# UKU208_power_board.net
KiCad netlist of a schematic drawn in Altium Designer
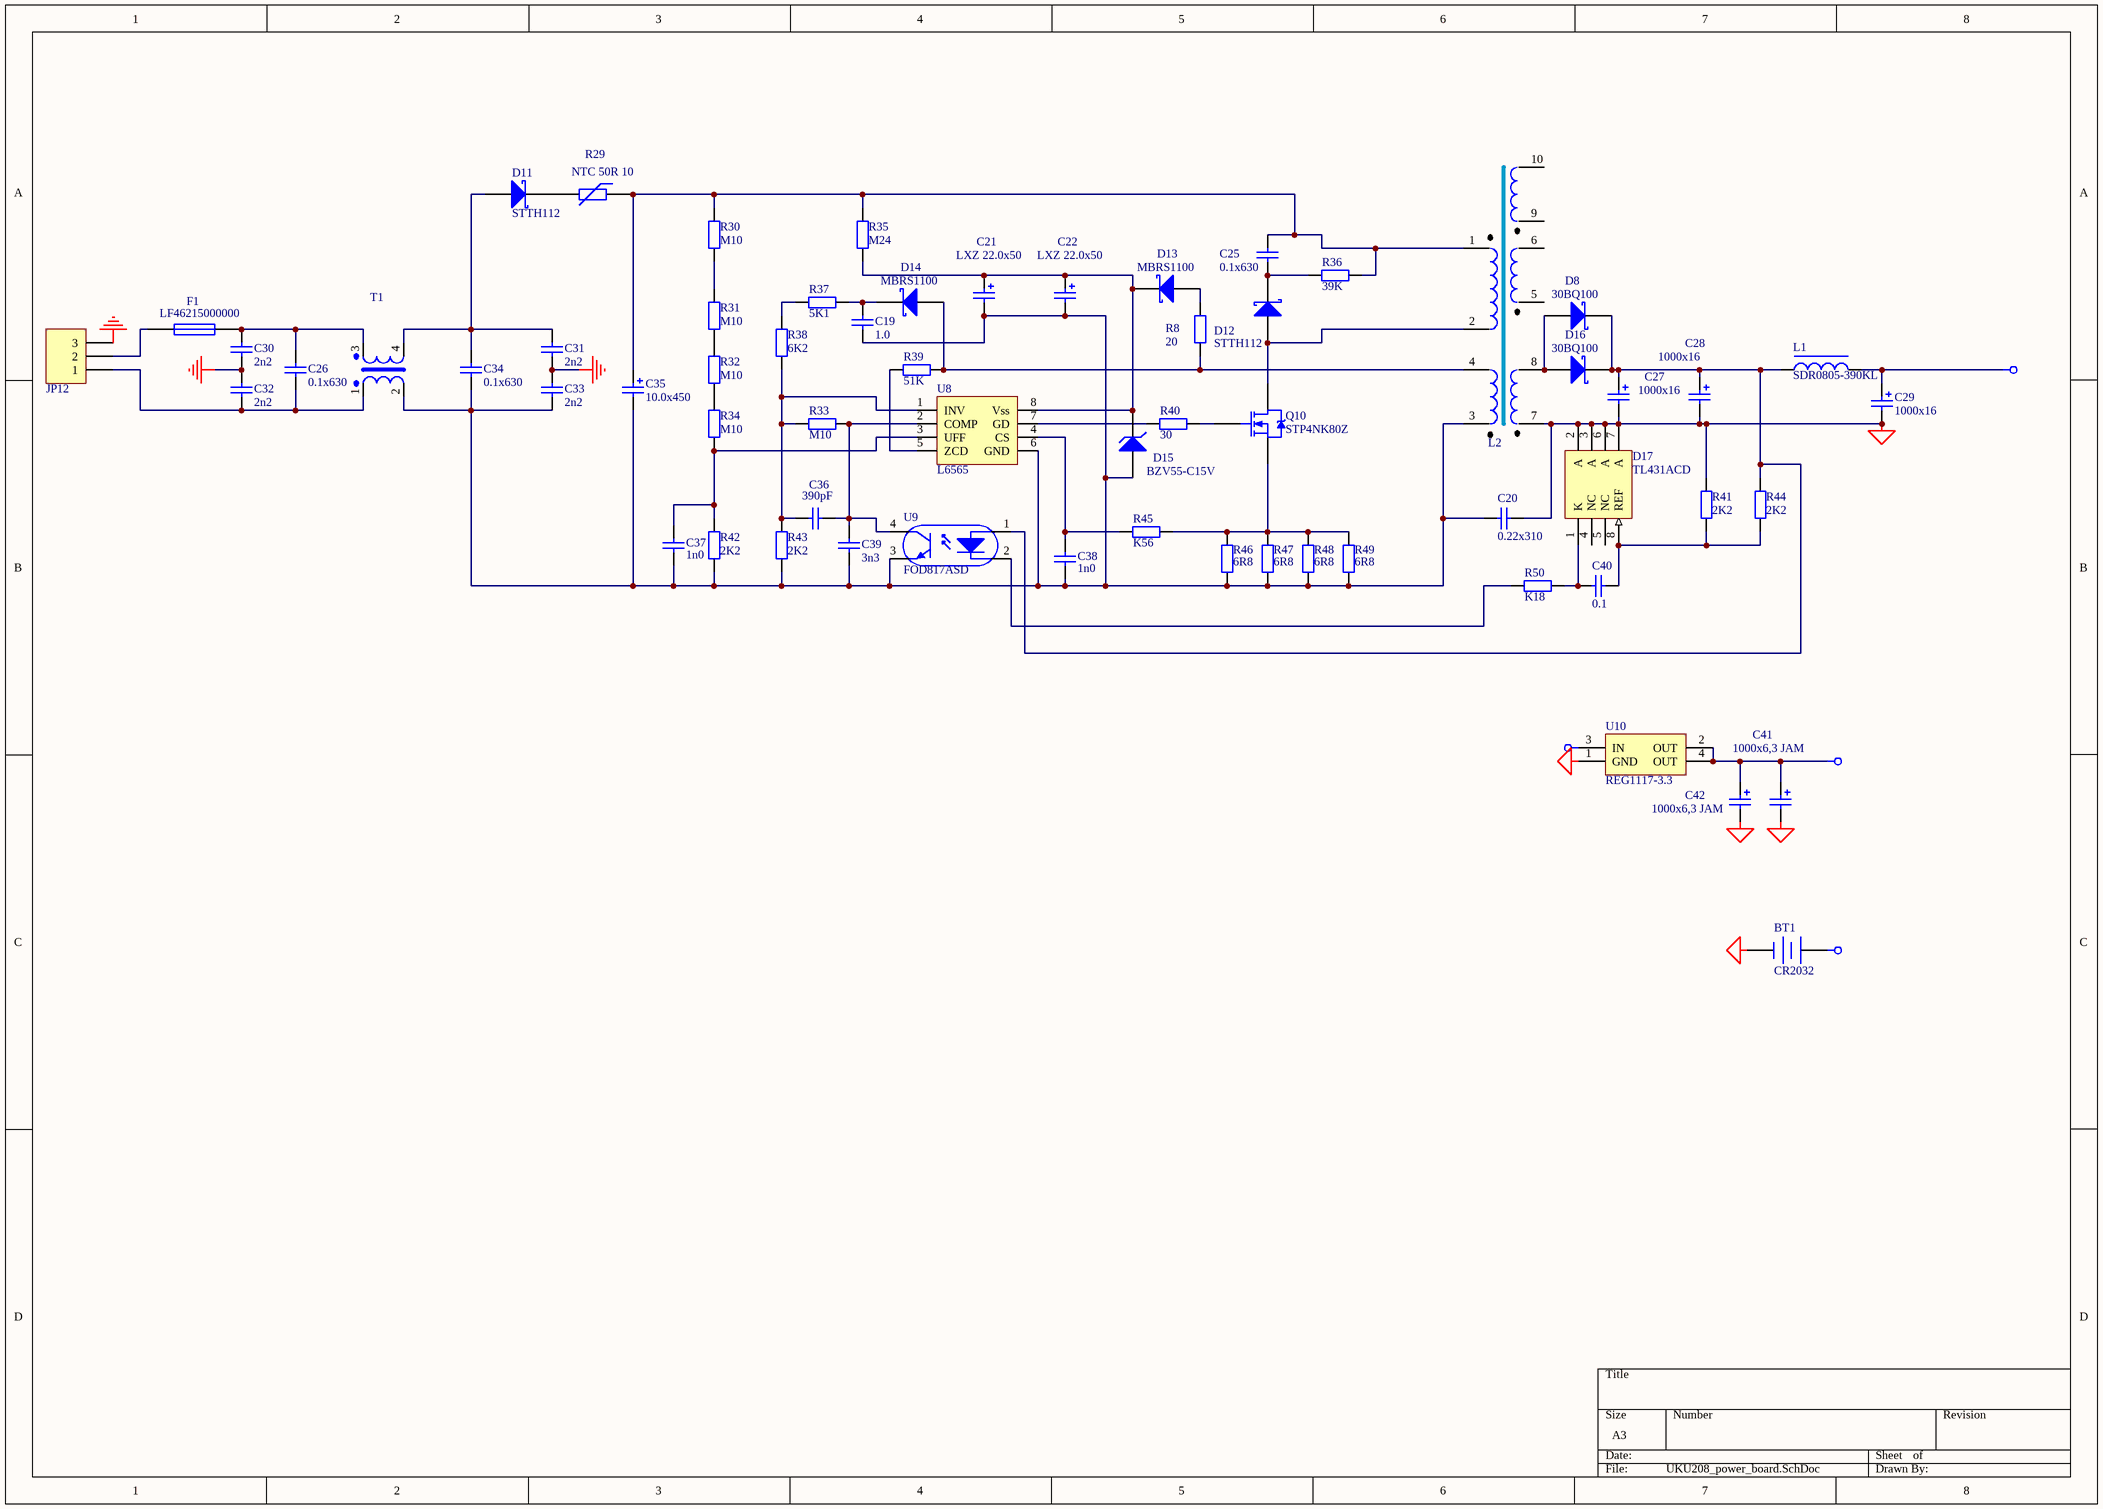
[diagram p0: UKU208_power_board.SchDoc]

(export (version "E")
  (design (tool "Eeschema 10.0.6"))
  (components
    (comp (ref "BT1")
      (value "CR2032")
      (footprint "BAT_SUPP")
      (description "Multicell Battery")
      (fields (field (name "MANUFACTURER") "Generic Components") (field (name "PUBLISHER") "Altium Limited"))
      (libsource (lib "Miscellaneous Devices") (part "Battery"))
    )
    (comp (ref "C19")
      (value "1.0")
      (footprint "_1206")
      (description "Capacitor (Semiconductor SIM Model)")
      (fields (field (name "MANUFACTURER") "Generic Components") (field (name "PUBLISHER") "Altium Limited"))
      (libsource (lib "Miscellaneous Devices") (part "Cap Semi"))
    )
    (comp (ref "C20")
      (value "0.22x310")
      (footprint "C8")
      (description "Capacitor (Semiconductor SIM Model)")
      (fields (field (name "MANUFACTURER") "Generic Components") (field (name "PUBLISHER") "Altium Limited"))
      (libsource (lib "Miscellaneous Devices") (part "Cap Semi"))
    )
    (comp (ref "C21")
      (value "LXZ 22.0x50")
      (footprint "el3")
      (description "Polarized Capacitor (Radial)")
      (fields (field (name "MANUFACTURER") "Generic Components") (field (name "PUBLISHER") "Altium Limited"))
      (libsource (lib "PAL") (part "Cap Pol1"))
    )
    (comp (ref "C22")
      (value "LXZ 22.0x50")
      (footprint "el3")
      (description "Polarized Capacitor (Radial)")
      (fields (field (name "MANUFACTURER") "Generic Components") (field (name "PUBLISHER") "Altium Limited"))
      (libsource (lib "PAL") (part "Cap Pol1"))
    )
    (comp (ref "C25")
      (value "0.1x630")
      (footprint "c15")
      (description "Capacitor (Semiconductor SIM Model)")
      (fields (field (name "MANUFACTURER") "Generic Components") (field (name "PUBLISHER") "Altium Limited"))
      (libsource (lib "Miscellaneous Devices") (part "Cap Semi"))
    )
    (comp (ref "C26")
      (value "0.1x630")
      (footprint "c15")
      (description "Capacitor (Semiconductor SIM Model)")
      (fields (field (name "MANUFACTURER") "Generic Components") (field (name "PUBLISHER") "Altium Limited"))
      (libsource (lib "Miscellaneous Devices") (part "Cap Semi"))
    )
    (comp (ref "C27")
      (value "1000x16")
      (footprint "el5")
      (description "Polarized Capacitor (Radial)")
      (fields (field (name "MANUFACTURER") "Generic Components") (field (name "PUBLISHER") "Altium Limited"))
      (libsource (lib "PAL") (part "Cap Pol1"))
    )
    (comp (ref "C28")
      (value "1000x16")
      (footprint "el5")
      (description "Polarized Capacitor (Radial)")
      (fields (field (name "MANUFACTURER") "Generic Components") (field (name "PUBLISHER") "Altium Limited"))
      (libsource (lib "PAL") (part "Cap Pol1"))
    )
    (comp (ref "C29")
      (value "1000x16")
      (footprint "el5")
      (description "Polarized Capacitor (Radial)")
      (fields (field (name "MANUFACTURER") "Generic Components") (field (name "PUBLISHER") "Altium Limited"))
      (libsource (lib "PAL") (part "Cap Pol1"))
    )
    (comp (ref "C30")
      (value "2n2")
      (footprint "C8")
      (description "Capacitor (Semiconductor SIM Model)")
      (fields (field (name "MANUFACTURER") "Generic Components") (field (name "PUBLISHER") "Altium Limited"))
      (libsource (lib "Miscellaneous Devices") (part "Cap Semi"))
    )
    (comp (ref "C31")
      (value "2n2")
      (footprint "c8")
      (description "Capacitor (Semiconductor SIM Model)")
      (fields (field (name "MANUFACTURER") "Generic Components") (field (name "PUBLISHER") "Altium Limited"))
      (libsource (lib "Miscellaneous Devices") (part "Cap Semi"))
    )
    (comp (ref "C32")
      (value "2n2")
      (footprint "c8")
      (description "Capacitor (Semiconductor SIM Model)")
      (fields (field (name "MANUFACTURER") "Generic Components") (field (name "PUBLISHER") "Altium Limited"))
      (libsource (lib "Miscellaneous Devices") (part "Cap Semi"))
    )
    (comp (ref "C33")
      (value "2n2")
      (footprint "c8")
      (description "Capacitor (Semiconductor SIM Model)")
      (fields (field (name "MANUFACTURER") "Generic Components") (field (name "PUBLISHER") "Altium Limited"))
      (libsource (lib "Miscellaneous Devices") (part "Cap Semi"))
    )
    (comp (ref "C34")
      (value "0.1x630")
      (footprint "c15")
      (description "Capacitor (Semiconductor SIM Model)")
      (fields (field (name "MANUFACTURER") "Generic Components") (field (name "PUBLISHER") "Altium Limited"))
      (libsource (lib "Miscellaneous Devices") (part "Cap Semi"))
    )
    (comp (ref "C35")
      (value "10.0x450")
      (footprint "el_15_25_h")
      (description "Polarized Capacitor (Radial)")
      (fields (field (name "MANUFACTURER") "Generic Components") (field (name "PUBLISHER") "Altium Limited"))
      (libsource (lib "PAL") (part "Cap Pol1"))
    )
    (comp (ref "C36")
      (value "390pF")
      (footprint "_1206")
      (description "Capacitor (Semiconductor SIM Model)")
      (fields (field (name "MANUFACTURER") "Generic Components") (field (name "PUBLISHER") "Altium Limited"))
      (libsource (lib "Miscellaneous Devices") (part "Cap Semi"))
    )
    (comp (ref "C37")
      (value "1n0")
      (footprint "_1206")
      (description "Capacitor (Semiconductor SIM Model)")
      (fields (field (name "MANUFACTURER") "Generic Components") (field (name "PUBLISHER") "Altium Limited"))
      (libsource (lib "Miscellaneous Devices") (part "Cap Semi"))
    )
    (comp (ref "C38")
      (value "1n0")
      (footprint "_1206")
      (description "Capacitor (Semiconductor SIM Model)")
      (fields (field (name "MANUFACTURER") "Generic Components") (field (name "PUBLISHER") "Altium Limited"))
      (libsource (lib "Miscellaneous Devices") (part "Cap Semi"))
    )
    (comp (ref "C39")
      (value "3n3")
      (footprint "_1206")
      (description "Capacitor (Semiconductor SIM Model)")
      (fields (field (name "MANUFACTURER") "Generic Components") (field (name "PUBLISHER") "Altium Limited"))
      (libsource (lib "Miscellaneous Devices") (part "Cap Semi"))
    )
    (comp (ref "C40")
      (value "0.1")
      (footprint "_1206")
      (description "Capacitor (Semiconductor SIM Model)")
      (fields (field (name "MANUFACTURER") "Generic Components") (field (name "PUBLISHER") "Altium Limited"))
      (libsource (lib "Miscellaneous Devices") (part "Cap Semi"))
    )
    (comp (ref "C41")
      (value "1000x6,3 JAM")
      (footprint "el3")
      (description "Polarized Capacitor (Radial)")
      (fields (field (name "MANUFACTURER") "Generic Components") (field (name "PUBLISHER") "Altium Limited"))
      (libsource (lib "PAL") (part "Cap Pol1"))
    )
    (comp (ref "C42")
      (value "1000x6,3 JAM")
      (footprint "el3")
      (description "Polarized Capacitor (Radial)")
      (fields (field (name "MANUFACTURER") "Generic Components") (field (name "PUBLISHER") "Altium Limited"))
      (libsource (lib "PAL") (part "Cap Pol1"))
    )
    (comp (ref "D8")
      (value "30BQ100")
      (footprint "30BQ100")
      (description "Schottky Rectifier")
      (fields
        (field (name "MANUFACTURER") "International Rectifier")
        (field (name "PUBLISHER") "Altium Limited")
      )
      (libsource (lib "IR Discrete Diode") (part "10BQ015"))
    )
    (comp (ref "D11")
      (value "STTH112")
      (footprint "D_6_3")
      (description "Schottky Diode")
      (fields
        (field (name "MANUFACTURER") "International Rectifier")
        (field (name "PUBLISHER") "Altium Limited")
      )
      (libsource (lib "IR Discrete Diode") (part "10BQ015"))
    )
    (comp (ref "D12")
      (value "STTH112")
      (footprint "D_6_3")
      (description "Schottky Diode")
      (fields
        (field (name "MANUFACTURER") "International Rectifier")
        (field (name "PUBLISHER") "Altium Limited")
      )
      (libsource (lib "IR Discrete Diode") (part "10BQ015"))
    )
    (comp (ref "D13")
      (value "MBRS1100")
      (footprint "D_6_3")
      (description "Schottky Rectifier")
      (fields
        (field (name "MANUFACTURER") "International Rectifier")
        (field (name "PUBLISHER") "Altium Limited")
      )
      (libsource (lib "IR Discrete Diode") (part "10BQ015"))
    )
    (comp (ref "D14")
      (value "MBRS1100")
      (footprint "D_6_3")
      (description "Schottky Rectifier")
      (fields
        (field (name "MANUFACTURER") "International Rectifier")
        (field (name "PUBLISHER") "Altium Limited")
      )
      (libsource (lib "IR Discrete Diode") (part "10BQ015"))
    )
    (comp (ref "D15")
      (value "BZV55-C15V")
      (footprint "_1206d")
      (description "Zener Diode")
      (fields (field (name "MANUFACTURER") "Generic Components") (field (name "PUBLISHER") "Altium Limited"))
      (libsource (lib "Miscellaneous Devices") (part "D Zener"))
    )
    (comp (ref "D16")
      (value "30BQ100")
      (footprint "30BQ100")
      (description "Schottky Rectifier")
      (fields
        (field (name "MANUFACTURER") "International Rectifier")
        (field (name "PUBLISHER") "Altium Limited")
      )
      (libsource (lib "IR Discrete Diode") (part "10BQ015"))
    )
    (comp (ref "D17")
      (value "TL431ACD")
      (footprint "SO-G8")
      (description "Programmable Precision Reference")
      (fields (field (name "MANUFACTURER") "Motorola") (field (name "PUBLISHER") "Altium Limited"))
      (libsource (lib "Motorola Power Management Voltage Reference") (part "TL431ACD"))
    )
    (comp (ref "F1")
      (value "LF46215000000")
      (footprint "LF462")
      (description "Fuse")
      (fields (field (name "MANUFACTURER") "Generic Components") (field (name "PUBLISHER") "Altium Limited"))
      (libsource (lib "Miscellaneous Devices") (part "Fuse 1"))
    )
    (comp (ref "JP12")
      (value "Header 3")
      (footprint "2EDGR-5.08-3P")
      (description "Header, 3-Pin")
      (fields (field (name "MANUFACTURER") "Generic Components") (field (name "PUBLISHER") "Altium Limited"))
      (libsource (lib "Miscellaneous Connectors") (part "Header 3"))
    )
    (comp (ref "L1")
      (value "SDR0805-390KL")
      (footprint "L10x10")
      (description "Magnetic-Core Inductor")
      (fields (field (name "MANUFACTURER") "Generic Components") (field (name "PUBLISHER") "Altium Limited"))
      (libsource (lib "PAL") (part "Inductor Konstr 2"))
    )
    (comp (ref "L2")
      (value "L220-K10")
      (footprint "trans_ring1")
      (description "Дроссель")
      (libsource (lib "PAL") (part "L1_dc_2"))
    )
    (comp (ref "Q10")
      (value "STP4NK80Z")
      (footprint "TO220_h")
      (description "N-Channel Power MOSFET")
      (fields (field (name "MANUFACTURER") "Generic Components") (field (name "PUBLISHER") "Altium Limited"))
      (libsource (lib "Miscellaneous Devices") (part "NMOS-2"))
    )
    (comp (ref "R8")
      (value "20")
      (footprint "_1206")
      (description "Resistor")
      (fields (field (name "MANUFACTURER") "Generic Components") (field (name "PUBLISHER") "Altium Limited"))
      (libsource (lib "") (part "Res2_2"))
    )
    (comp (ref "R29")
      (value "NTC 50R 10")
      (footprint "JVR07N")
      (description "Varistor (Voltage-Sensitive Resistor)")
      (fields (field (name "MANUFACTURER") "Generic Components") (field (name "PUBLISHER") "Altium Limited"))
      (libsource (lib "Miscellaneous Devices") (part "Res Varistor"))
    )
    (comp (ref "R30")
      (value "M10")
      (footprint "_1206")
      (description "Resistor")
      (fields (field (name "MANUFACTURER") "Generic Components") (field (name "PUBLISHER") "Altium Limited"))
      (libsource (lib "") (part "Res2_1"))
    )
    (comp (ref "R31")
      (value "M10")
      (footprint "_1206")
      (description "Resistor")
      (fields (field (name "MANUFACTURER") "Generic Components") (field (name "PUBLISHER") "Altium Limited"))
      (libsource (lib "") (part "Res2_1"))
    )
    (comp (ref "R32")
      (value "M10")
      (footprint "_1206")
      (description "Resistor")
      (fields (field (name "MANUFACTURER") "Generic Components") (field (name "PUBLISHER") "Altium Limited"))
      (libsource (lib "") (part "Res2_1"))
    )
    (comp (ref "R33")
      (value "M10")
      (footprint "_1206")
      (description "Resistor")
      (fields (field (name "MANUFACTURER") "Generic Components") (field (name "PUBLISHER") "Altium Limited"))
      (libsource (lib "Miscellaneous Devices") (part "Res2"))
    )
    (comp (ref "R34")
      (value "M10")
      (footprint "_1206")
      (description "Resistor")
      (fields (field (name "MANUFACTURER") "Generic Components") (field (name "PUBLISHER") "Altium Limited"))
      (libsource (lib "") (part "Res2_1"))
    )
    (comp (ref "R35")
      (value "M24")
      (footprint "AXIAL-0.7")
      (description "Resistor")
      (fields (field (name "MANUFACTURER") "Generic Components") (field (name "PUBLISHER") "Altium Limited"))
      (libsource (lib "") (part "Res2_1"))
    )
    (comp (ref "R36")
      (value "39K")
      (footprint "AXIAL-0.7")
      (description "Resistor")
      (fields (field (name "MANUFACTURER") "Generic Components") (field (name "PUBLISHER") "Altium Limited"))
      (libsource (lib "Miscellaneous Devices") (part "Res2"))
    )
    (comp (ref "R37")
      (value "5K1")
      (footprint "_1206")
      (description "Resistor")
      (fields (field (name "MANUFACTURER") "Generic Components") (field (name "PUBLISHER") "Altium Limited"))
      (libsource (lib "Miscellaneous Devices") (part "Res2"))
    )
    (comp (ref "R38")
      (value "6K2")
      (footprint "_1206")
      (description "Resistor")
      (fields (field (name "MANUFACTURER") "Generic Components") (field (name "PUBLISHER") "Altium Limited"))
      (libsource (lib "") (part "Res2_1"))
    )
    (comp (ref "R39")
      (value "51K")
      (footprint "_1206")
      (description "Resistor")
      (fields (field (name "MANUFACTURER") "Generic Components") (field (name "PUBLISHER") "Altium Limited"))
      (libsource (lib "Miscellaneous Devices") (part "Res2"))
    )
    (comp (ref "R40")
      (value "30")
      (footprint "_1206")
      (description "Resistor")
      (fields (field (name "MANUFACTURER") "Generic Components") (field (name "PUBLISHER") "Altium Limited"))
      (libsource (lib "Miscellaneous Devices") (part "Res2"))
    )
    (comp (ref "R41")
      (value "2K2")
      (footprint "_1206")
      (description "Resistor")
      (fields (field (name "MANUFACTURER") "Generic Components") (field (name "PUBLISHER") "Altium Limited"))
      (libsource (lib "") (part "Res2_1"))
    )
    (comp (ref "R42")
      (value "2K2")
      (footprint "_1206")
      (description "Resistor")
      (fields (field (name "MANUFACTURER") "Generic Components") (field (name "PUBLISHER") "Altium Limited"))
      (libsource (lib "") (part "Res2_1"))
    )
    (comp (ref "R43")
      (value "2K2")
      (footprint "_1206")
      (description "Resistor")
      (fields (field (name "MANUFACTURER") "Generic Components") (field (name "PUBLISHER") "Altium Limited"))
      (libsource (lib "") (part "Res2_1"))
    )
    (comp (ref "R44")
      (value "2K2")
      (footprint "_1206")
      (description "Resistor")
      (fields (field (name "MANUFACTURER") "Generic Components") (field (name "PUBLISHER") "Altium Limited"))
      (libsource (lib "") (part "Res2_2"))
    )
    (comp (ref "R45")
      (value "K56")
      (footprint "_1206")
      (description "Resistor")
      (fields (field (name "MANUFACTURER") "Generic Components") (field (name "PUBLISHER") "Altium Limited"))
      (libsource (lib "Miscellaneous Devices") (part "Res2"))
    )
    (comp (ref "R46")
      (value "6R8")
      (footprint "_1206")
      (description "Resistor")
      (fields (field (name "MANUFACTURER") "Generic Components") (field (name "PUBLISHER") "Altium Limited"))
      (libsource (lib "") (part "Res2_2"))
    )
    (comp (ref "R47")
      (value "6R8")
      (footprint "_1206")
      (description "Resistor")
      (fields (field (name "MANUFACTURER") "Generic Components") (field (name "PUBLISHER") "Altium Limited"))
      (libsource (lib "") (part "Res2_2"))
    )
    (comp (ref "R48")
      (value "6R8")
      (footprint "_1206")
      (description "Resistor")
      (fields (field (name "MANUFACTURER") "Generic Components") (field (name "PUBLISHER") "Altium Limited"))
      (libsource (lib "") (part "Res2_2"))
    )
    (comp (ref "R49")
      (value "6R8")
      (footprint "_1206")
      (description "Resistor")
      (fields (field (name "MANUFACTURER") "Generic Components") (field (name "PUBLISHER") "Altium Limited"))
      (libsource (lib "") (part "Res2_2"))
    )
    (comp (ref "R50")
      (value "K18")
      (footprint "_1206")
      (description "Resistor")
      (fields (field (name "MANUFACTURER") "Generic Components") (field (name "PUBLISHER") "Altium Limited"))
      (libsource (lib "Miscellaneous Devices") (part "Res2"))
    )
    (comp (ref "T1")
      (value "TRANS1_1")
      (footprint "3030R4")
      (fields (field (name "MANUFACTURER") "Generic Components") (field (name "PUBLISHER") "Altium Limited"))
      (libsource (lib "PAL") (part "TRANS1_1"))
    )
    (comp (ref "U8") (value "L6565") (footprint "so-g8") (libsource (lib "PAL") (part "L6565")))
    (comp (ref "U9") (value "FOD817ASD") (footprint "FOD817ASD") (libsource (lib "PAL") (part "F00817ASD")))
    (comp (ref "U10")
      (value "REG1117-3.3")
      (footprint "DSO-G3")
      (description "800mA and 1A Low Dropout Positive Regulator 2.85V, 3.3V, 5V, and Adjustable")
      (fields (field (name "MANUFACTURER") "Burr-Brown") (field (name "PUBLISHER") "Altium Limited"))
      (libsource (lib "BB Power Mgt Voltage Regulator") (part "REG1117-3.3"))
    )
  )
  (nets
    (net (code "1") (name "+3v3") (class "Default")
      (node (ref "C41") (pin "1") (pinfunction "1_1") (pintype "passive"))
      (node (ref "C42") (pin "1") (pinfunction "1_1") (pintype "passive"))
      (node (ref "U10") (pin "2") (pinfunction "OUT_2") (pintype "power_in"))
      (node (ref "U10") (pin "4") (pinfunction "OUT_4") (pintype "power_in"))
    )
    (net (code "2") (name "+5v") (class "Default")
      (node (ref "C29") (pin "1") (pinfunction "1_1") (pintype "passive"))
      (node (ref "L1") (pin "2") (pinfunction "2_2") (pintype "passive"))
      (node (ref "U10") (pin "3") (pinfunction "IN_3") (pintype "power_in"))
    )
    (net (code "3") (name "+Vbat") (class "Default")
      (node (ref "BT1") (pin "1") (pinfunction "+_1") (pintype "passive"))
    )
    (net (code "4") (name "GND") (class "Default")
      (node (ref "BT1") (pin "2") (pinfunction "-_2") (pintype "passive"))
      (node (ref "C20") (pin "1") (pinfunction "1_1") (pintype "passive"))
      (node (ref "C27") (pin "2") (pinfunction "2_2") (pintype "passive"))
      (node (ref "C28") (pin "2") (pinfunction "2_2") (pintype "passive"))
      (node (ref "C29") (pin "2") (pinfunction "2_2") (pintype "passive"))
      (node (ref "C41") (pin "2") (pinfunction "2_2") (pintype "passive"))
      (node (ref "C42") (pin "2") (pinfunction "2_2") (pintype "passive"))
      (node (ref "D17") (pin "2") (pinfunction "A_2") (pintype "passive"))
      (node (ref "D17") (pin "3") (pinfunction "A_3") (pintype "passive"))
      (node (ref "D17") (pin "6") (pinfunction "A_6") (pintype "passive"))
      (node (ref "D17") (pin "7") (pinfunction "A_7") (pintype "passive"))
      (node (ref "L2") (pin "7") (pintype "passive"))
      (node (ref "R41") (pin "2") (pinfunction "2_2") (pintype "passive"))
      (node (ref "U10") (pin "1") (pinfunction "GND_1") (pintype "power_in"))
    )
    (net (code "5") (name "GND_GND") (class "Default")
      (node (ref "C30") (pin "1") (pinfunction "1_1") (pintype "passive"))
      (node (ref "C31") (pin "1") (pinfunction "1_1") (pintype "passive"))
      (node (ref "C32") (pin "2") (pinfunction "2_2") (pintype "passive"))
      (node (ref "C33") (pin "2") (pinfunction "2_2") (pintype "passive"))
      (node (ref "JP12") (pin "3") (pinfunction "3_3") (pintype "passive"))
    )
    (net (code "6") (name "Net-(C25-Pad2)") (class "Default")
      (node (ref "C25") (pin "2") (pinfunction "2_2") (pintype "passive"))
      (node (ref "C35") (pin "1") (pinfunction "1_1") (pintype "passive"))
      (node (ref "L2") (pin "1") (pintype "passive"))
      (node (ref "R29") (pin "1") (pinfunction "1_1") (pintype "passive"))
      (node (ref "R30") (pin "2") (pinfunction "2_2") (pintype "passive"))
      (node (ref "R35") (pin "2") (pinfunction "2_2") (pintype "passive"))
      (node (ref "R36") (pin "1") (pinfunction "1_1") (pintype "passive"))
    )
    (net (code "7") (name "Net-(D11-A)") (class "Default")
      (node (ref "C31") (pin "2") (pinfunction "2_2") (pintype "passive"))
      (node (ref "C34") (pin "2") (pinfunction "2_2") (pintype "passive"))
      (node (ref "D11") (pin "1") (pinfunction "A_1") (pintype "passive"))
      (node (ref "T1") (pin "4") (pinfunction "Sec1-_4") (pintype "passive"))
    )
    (net (code "8") (name "Net-(D11-K)") (class "Default")
      (node (ref "D11") (pin "2") (pinfunction "K_2") (pintype "passive"))
      (node (ref "R29") (pin "2") (pinfunction "2_2") (pintype "passive"))
    )
    (net (code "9") (name "Net-(D12-A)") (class "Default")
      (node (ref "D12") (pin "1") (pinfunction "A_1") (pintype "passive"))
      (node (ref "L2") (pin "2") (pintype "passive"))
      (node (ref "Q10") (pin "2") (pinfunction "D_2") (pintype "passive"))
    )
    (net (code "10") (name "Net-(D12-K)") (class "Default")
      (node (ref "C25") (pin "1") (pinfunction "1_1") (pintype "passive"))
      (node (ref "D12") (pin "2") (pinfunction "K_2") (pintype "passive"))
      (node (ref "R36") (pin "2") (pinfunction "2_2") (pintype "passive"))
    )
    (net (code "11") (name "Net-(D13-A)") (class "Default")
      (node (ref "D13") (pin "1") (pinfunction "A_1") (pintype "passive"))
      (node (ref "R8") (pin "1") (pinfunction "1_1") (pintype "passive"))
    )
    (net (code "12") (name "Net-(D13-K)") (class "Default")
      (node (ref "C21") (pin "1") (pinfunction "1_1") (pintype "passive"))
      (node (ref "C22") (pin "1") (pinfunction "1_1") (pintype "passive"))
      (node (ref "D13") (pin "2") (pinfunction "K_2") (pintype "passive"))
      (node (ref "D15") (pin "2") (pinfunction "K_2") (pintype "passive"))
      (node (ref "R35") (pin "1") (pinfunction "1_1") (pintype "passive"))
      (node (ref "U8") (pin "8") (pinfunction "Vss_8") (pintype "passive"))
    )
    (net (code "13") (name "Net-(D14-A)") (class "Default")
      (node (ref "D14") (pin "1") (pinfunction "A_1") (pintype "passive"))
      (node (ref "L2") (pin "4") (pintype "passive"))
      (node (ref "R39") (pin "1") (pinfunction "1_1") (pintype "passive"))
      (node (ref "R8") (pin "2") (pinfunction "2_2") (pintype "passive"))
    )
    (net (code "14") (name "Net-(D14-K)") (class "Default")
      (node (ref "C19") (pin "2") (pinfunction "2_2") (pintype "passive"))
      (node (ref "D14") (pin "2") (pinfunction "K_2") (pintype "passive"))
      (node (ref "R37") (pin "1") (pinfunction "1_1") (pintype "passive"))
    )
    (net (code "15") (name "Net-(D15-A)") (class "Default")
      (node (ref "C19") (pin "1") (pinfunction "1_1") (pintype "passive"))
      (node (ref "C20") (pin "2") (pinfunction "2_2") (pintype "passive"))
      (node (ref "C21") (pin "2") (pinfunction "2_2") (pintype "passive"))
      (node (ref "C22") (pin "2") (pinfunction "2_2") (pintype "passive"))
      (node (ref "C33") (pin "1") (pinfunction "1_1") (pintype "passive"))
      (node (ref "C34") (pin "1") (pinfunction "1_1") (pintype "passive"))
      (node (ref "C35") (pin "2") (pinfunction "2_2") (pintype "passive"))
      (node (ref "C37") (pin "2") (pinfunction "2_2") (pintype "passive"))
      (node (ref "C38") (pin "2") (pinfunction "2_2") (pintype "passive"))
      (node (ref "C39") (pin "1") (pinfunction "1_1") (pintype "passive"))
      (node (ref "D15") (pin "1") (pinfunction "A_1") (pintype "passive"))
      (node (ref "L2") (pin "3") (pintype "passive"))
      (node (ref "R42") (pin "1") (pinfunction "1_1") (pintype "passive"))
      (node (ref "R43") (pin "1") (pinfunction "1_1") (pintype "passive"))
      (node (ref "R46") (pin "2") (pinfunction "2_2") (pintype "passive"))
      (node (ref "R47") (pin "2") (pinfunction "2_2") (pintype "passive"))
      (node (ref "R48") (pin "2") (pinfunction "2_2") (pintype "passive"))
      (node (ref "R49") (pin "2") (pinfunction "2_2") (pintype "passive"))
      (node (ref "T1") (pin "2") (pinfunction "Pri-_2") (pintype "passive"))
      (node (ref "U8") (pin "6") (pinfunction "GND_6") (pintype "passive"))
      (node (ref "U9") (pin "3") (pinfunction "4_3") (pintype "passive"))
    )
    (net (code "16") (name "Net-(D16-A)") (class "Default")
      (node (ref "D16") (pin "1") (pinfunction "A_1") (pintype "passive"))
      (node (ref "D8") (pin "1") (pinfunction "A_1") (pintype "passive"))
      (node (ref "L2") (pin "8") (pintype "passive"))
    )
    (net (code "17") (name "Net-(D16-K)") (class "Default")
      (node (ref "C27") (pin "1") (pinfunction "1_1") (pintype "passive"))
      (node (ref "C28") (pin "1") (pinfunction "1_1") (pintype "passive"))
      (node (ref "D16") (pin "2") (pinfunction "K_2") (pintype "passive"))
      (node (ref "D8") (pin "2") (pinfunction "K_2") (pintype "passive"))
      (node (ref "L1") (pin "1") (pinfunction "1_1") (pintype "passive"))
      (node (ref "R44") (pin "1") (pinfunction "1_1") (pintype "passive"))
      (node (ref "U9") (pin "1") (pinfunction "0_1") (pintype "passive"))
    )
    (net (code "18") (name "Net-(D17-K)") (class "Default")
      (node (ref "C40") (pin "2") (pinfunction "2_2") (pintype "passive"))
      (node (ref "D17") (pin "1") (pinfunction "K_1") (pintype "passive"))
      (node (ref "R50") (pin "1") (pinfunction "1_1") (pintype "passive"))
    )
    (net (code "19") (name "Net-(D17-REF)") (class "Default")
      (node (ref "C40") (pin "1") (pinfunction "1_1") (pintype "passive"))
      (node (ref "D17") (pin "8") (pinfunction "REF_8") (pintype "input"))
      (node (ref "R41") (pin "1") (pinfunction "1_1") (pintype "passive"))
      (node (ref "R44") (pin "2") (pinfunction "2_2") (pintype "passive"))
    )
    (net (code "20") (name "Net-(F1-Pad2)") (class "Default")
      (node (ref "F1") (pin "2") (pinfunction "2_2") (pintype "passive"))
      (node (ref "JP12") (pin "2") (pinfunction "2_2") (pintype "passive"))
    )
    (net (code "21") (name "Net-(Q10-G)") (class "Default")
      (node (ref "Q10") (pin "1") (pinfunction "G_1") (pintype "passive"))
      (node (ref "R40") (pin "1") (pinfunction "1_1") (pintype "passive"))
    )
    (net (code "22") (name "Net-(Q10-S)") (class "Default")
      (node (ref "Q10") (pin "3") (pinfunction "S_3") (pintype "passive"))
      (node (ref "R45") (pin "1") (pinfunction "1_1") (pintype "passive"))
      (node (ref "R46") (pin "1") (pinfunction "1_1") (pintype "passive"))
      (node (ref "R47") (pin "1") (pinfunction "1_1") (pintype "passive"))
      (node (ref "R48") (pin "1") (pinfunction "1_1") (pintype "passive"))
      (node (ref "R49") (pin "1") (pinfunction "1_1") (pintype "passive"))
    )
    (net (code "23") (name "Net-(R30-Pad1)") (class "Default")
      (node (ref "R30") (pin "1") (pinfunction "1_1") (pintype "passive"))
      (node (ref "R31") (pin "2") (pinfunction "2_2") (pintype "passive"))
    )
    (net (code "24") (name "Net-(R31-Pad1)") (class "Default")
      (node (ref "R31") (pin "1") (pinfunction "1_1") (pintype "passive"))
      (node (ref "R32") (pin "2") (pinfunction "2_2") (pintype "passive"))
    )
    (net (code "25") (name "Net-(R32-Pad1)") (class "Default")
      (node (ref "R32") (pin "1") (pinfunction "1_1") (pintype "passive"))
      (node (ref "R34") (pin "2") (pinfunction "2_2") (pintype "passive"))
    )
    (net (code "26") (name "Net-(R37-Pad2)") (class "Default")
      (node (ref "R37") (pin "2") (pinfunction "2_2") (pintype "passive"))
      (node (ref "R38") (pin "2") (pinfunction "2_2") (pintype "passive"))
    )
    (net (code "27") (name "Net-(T1-Pri+)") (class "Default")
      (node (ref "C26") (pin "1") (pinfunction "1_1") (pintype "passive"))
      (node (ref "C32") (pin "1") (pinfunction "1_1") (pintype "passive"))
      (node (ref "JP12") (pin "1") (pinfunction "1_1") (pintype "passive"))
      (node (ref "T1") (pin "1") (pinfunction "Pri+_1") (pintype "passive"))
    )
    (net (code "28") (name "Net-(T1-Sec1+)") (class "Default")
      (node (ref "C26") (pin "2") (pinfunction "2_2") (pintype "passive"))
      (node (ref "C30") (pin "2") (pinfunction "2_2") (pintype "passive"))
      (node (ref "F1") (pin "1") (pinfunction "1_1") (pintype "passive"))
      (node (ref "T1") (pin "3") (pinfunction "Sec1+_3") (pintype "passive"))
    )
    (net (code "29") (name "Net-(U8-COMP)") (class "Default")
      (node (ref "C36") (pin "2") (pinfunction "2_2") (pintype "passive"))
      (node (ref "C39") (pin "2") (pinfunction "2_2") (pintype "passive"))
      (node (ref "R33") (pin "1") (pinfunction "1_1") (pintype "passive"))
      (node (ref "U8") (pin "2") (pinfunction "COMP_2") (pintype "passive"))
      (node (ref "U9") (pin "4") (pinfunction "2_4") (pintype "passive"))
    )
    (net (code "30") (name "Net-(U8-CS)") (class "Default")
      (node (ref "C38") (pin "1") (pinfunction "1_1") (pintype "passive"))
      (node (ref "R45") (pin "2") (pinfunction "2_2") (pintype "passive"))
      (node (ref "U8") (pin "4") (pinfunction "CS_4") (pintype "passive"))
    )
    (net (code "31") (name "Net-(U8-GD)") (class "Default")
      (node (ref "R40") (pin "2") (pinfunction "2_2") (pintype "passive"))
      (node (ref "U8") (pin "7") (pinfunction "GD_7") (pintype "passive"))
    )
    (net (code "32") (name "Net-(U8-INV)") (class "Default")
      (node (ref "C36") (pin "1") (pinfunction "1_1") (pintype "passive"))
      (node (ref "R33") (pin "2") (pinfunction "2_2") (pintype "passive"))
      (node (ref "R38") (pin "1") (pinfunction "1_1") (pintype "passive"))
      (node (ref "R43") (pin "2") (pinfunction "2_2") (pintype "passive"))
      (node (ref "U8") (pin "1") (pinfunction "INV_1") (pintype "passive"))
    )
    (net (code "33") (name "Net-(U8-UFF)") (class "Default")
      (node (ref "C37") (pin "1") (pinfunction "1_1") (pintype "passive"))
      (node (ref "R34") (pin "1") (pinfunction "1_1") (pintype "passive"))
      (node (ref "R42") (pin "2") (pinfunction "2_2") (pintype "passive"))
      (node (ref "U8") (pin "3") (pinfunction "UFF_3") (pintype "passive"))
    )
    (net (code "34") (name "Net-(U8-ZCD)") (class "Default")
      (node (ref "R39") (pin "2") (pinfunction "2_2") (pintype "passive"))
      (node (ref "U8") (pin "5") (pinfunction "ZCD_5") (pintype "passive"))
    )
    (net (code "35") (name "Net-(U9-1)") (class "Default")
      (node (ref "R50") (pin "2") (pinfunction "2_2") (pintype "passive"))
      (node (ref "U9") (pin "2") (pinfunction "1_2") (pintype "passive"))
    )
    (net (code "36") (name "unconnected-(D17-NC-Pad4)") (class "Default")
      (node (ref "D17") (pin "4") (pinfunction "NC_4") (pintype "passive"))
    )
    (net (code "37") (name "unconnected-(D17-NC-Pad5)") (class "Default")
      (node (ref "D17") (pin "5") (pinfunction "NC_5") (pintype "passive"))
    )
    (net (code "38") (name "unconnected-(L2-Pad5)") (class "Default")
      (node (ref "L2") (pin "5") (pintype "passive"))
    )
    (net (code "39") (name "unconnected-(L2-Pad6)") (class "Default")
      (node (ref "L2") (pin "6") (pintype "passive"))
    )
    (net (code "40") (name "unconnected-(L2-Pad9)") (class "Default")
      (node (ref "L2") (pin "9") (pintype "passive"))
    )
    (net (code "41") (name "unconnected-(L2-Pad10)") (class "Default")
      (node (ref "L2") (pin "10") (pinfunction "10_10") (pintype "passive"))
    )
  )
)
